# SENSE.net
KiCad netlist of a schematic drawn in Altium Designer
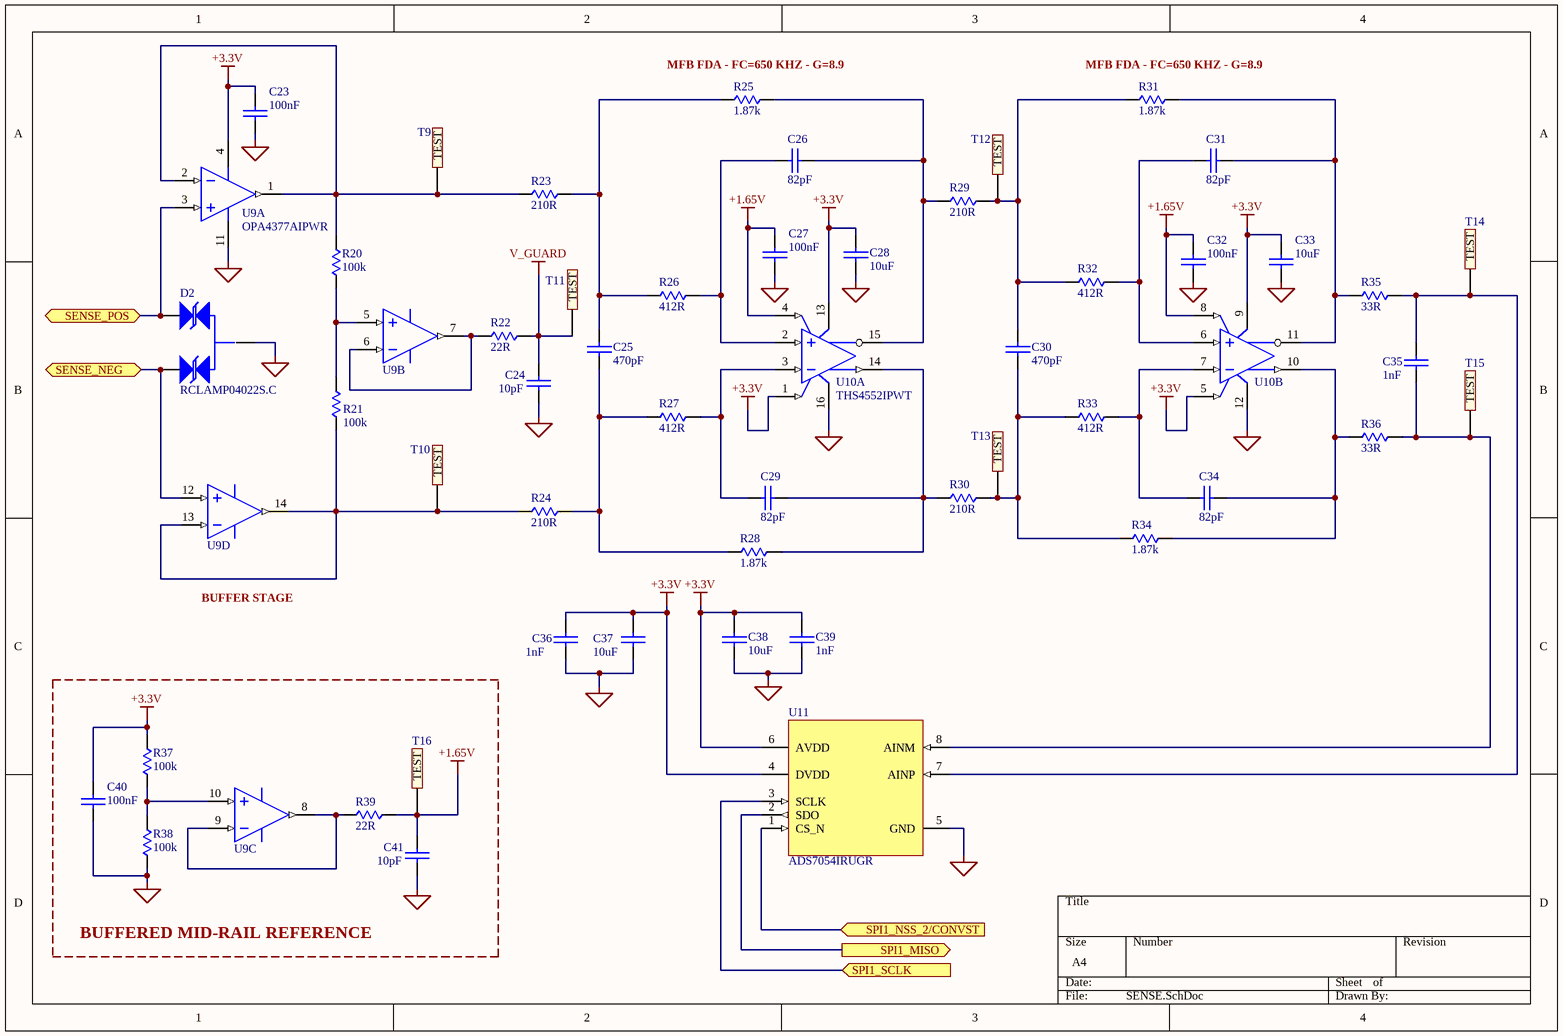
[diagram p0: SENSE.SchDoc]

(export (version "E")
  (design (tool "Eeschema 10.0.6"))
  (components
    (comp (ref "C23")
      (value "100nF")
      (footprint "0603-CAP")
      (description "CAP CER 100 NF 50V X7R 0603")
      (libsource (lib "SGL_Capacitors") (part "Capacitor"))
    )
    (comp (ref "C24")
      (value "10pF")
      (footprint "0603-CAP")
      (description "CAP CER 10PF 50V C0G/NPO 0603")
      (libsource (lib "SGL_Capacitors") (part "Capacitor"))
    )
    (comp (ref "C25")
      (value "470pF")
      (footprint "0603-CAP")
      (description "CAP CER 470PF 50V C0G 0603")
      (libsource (lib "SGL_Capacitors") (part "Capacitor"))
    )
    (comp (ref "C26")
      (value "82pF")
      (footprint "0603-CAP")
      (description "CAP CER 82PF 50V C0G 0603")
      (libsource (lib "SGL_Capacitors") (part "Capacitor"))
    )
    (comp (ref "C27")
      (value "100nF")
      (footprint "0603-CAP")
      (description "CAP CER 100 NF 50V X7R 0603")
      (libsource (lib "SGL_Capacitors") (part "Capacitor"))
    )
    (comp (ref "C28")
      (value "10uF")
      (footprint "0603-CAP")
      (description "CAP CER 10uF 6.3V X5R 0603")
      (libsource (lib "SGL_Capacitors") (part "Capacitor"))
    )
    (comp (ref "C29")
      (value "82pF")
      (footprint "0603-CAP")
      (description "CAP CER 82PF 50V C0G 0603")
      (libsource (lib "SGL_Capacitors") (part "Capacitor"))
    )
    (comp (ref "C30")
      (value "470pF")
      (footprint "0603-CAP")
      (description "CAP CER 470PF 50V C0G 0603")
      (libsource (lib "SGL_Capacitors") (part "Capacitor"))
    )
    (comp (ref "C31")
      (value "82pF")
      (footprint "0603-CAP")
      (description "CAP CER 82PF 50V C0G 0603")
      (libsource (lib "SGL_Capacitors") (part "Capacitor"))
    )
    (comp (ref "C32")
      (value "100nF")
      (footprint "0603-CAP")
      (description "CAP CER 100 NF 50V X7R 0603")
      (libsource (lib "SGL_Capacitors") (part "Capacitor"))
    )
    (comp (ref "C33")
      (value "10uF")
      (footprint "0603-CAP")
      (description "CAP CER 10uF 6.3V X5R 0603")
      (libsource (lib "SGL_Capacitors") (part "Capacitor"))
    )
    (comp (ref "C34")
      (value "82pF")
      (footprint "0603-CAP")
      (description "CAP CER 82PF 50V C0G 0603")
      (libsource (lib "SGL_Capacitors") (part "Capacitor"))
    )
    (comp (ref "C35")
      (value "1nF")
      (footprint "0603-CAP")
      (description "CAP CER 1000 PF 50V C0G 0603")
      (libsource (lib "SGL_Capacitors") (part "Capacitor"))
    )
    (comp (ref "C36")
      (value "1nF")
      (footprint "0603-CAP")
      (description "CAP CER 1000 PF 50V C0G 0603")
      (libsource (lib "SGL_Capacitors") (part "Capacitor"))
    )
    (comp (ref "C37")
      (value "10uF")
      (footprint "0603-CAP")
      (description "CAP CER 10uF 6.3V X5R 0603")
      (libsource (lib "SGL_Capacitors") (part "Capacitor"))
    )
    (comp (ref "C38")
      (value "10uF")
      (footprint "0603-CAP")
      (description "CAP CER 10uF 6.3V X5R 0603")
      (libsource (lib "SGL_Capacitors") (part "Capacitor"))
    )
    (comp (ref "C39")
      (value "1nF")
      (footprint "0603-CAP")
      (description "CAP CER 1000 PF 50V C0G 0603")
      (libsource (lib "SGL_Capacitors") (part "Capacitor"))
    )
    (comp (ref "C40")
      (value "100nF")
      (footprint "0603-CAP")
      (description "CAP CER 100 NF 50V X7R 0603")
      (libsource (lib "SGL_Capacitors") (part "Capacitor"))
    )
    (comp (ref "C41")
      (value "10pF")
      (footprint "0603-CAP")
      (description "CAP CER 10PF 50V C0G/NPO 0603")
      (libsource (lib "SGL_Capacitors") (part "Capacitor"))
    )
    (comp (ref "D2")
      (value "RCLAMP04022S.C")
      (footprint "SOT-23 3L")
      (libsource (lib "BioZ") (part "RCLAMP04022S.C"))
    )
    (comp (ref "R20")
      (value "100k")
      (footprint "0603-RES")
      (description "RES SMD 100KOHM 0.1% 1/10W 0603")
      (libsource (lib "SGL_Resistives") (part "RESISTOR"))
    )
    (comp (ref "R21")
      (value "100k")
      (footprint "0603-RES")
      (description "RES SMD 100KOHM 0.1% 1/10W 0603")
      (libsource (lib "SGL_Resistives") (part "RESISTOR"))
    )
    (comp (ref "R22")
      (value "22R")
      (footprint "0603-RES")
      (description "RES SMD 22OHM 0.1% 1/10W 0603")
      (libsource (lib "SGL_Resistives") (part "RESISTOR"))
    )
    (comp (ref "R23")
      (value "210R")
      (footprint "0603-RES")
      (description "RES SMD 210OHM 0.1% 1/10W 0603")
      (libsource (lib "SGL_Resistives") (part "RESISTOR"))
    )
    (comp (ref "R24")
      (value "210R")
      (footprint "0603-RES")
      (description "RES SMD 210OHM 0.1% 1/10W 0603")
      (libsource (lib "SGL_Resistives") (part "RESISTOR"))
    )
    (comp (ref "R25")
      (value "1.87k")
      (footprint "0603-RES")
      (description "RES SMD 1.87KOHM 0.1% 1/10W 0603")
      (libsource (lib "SGL_Resistives") (part "RESISTOR"))
    )
    (comp (ref "R26")
      (value "412R")
      (footprint "0603-RES")
      (description "RES SMD 412OHM 0.1% 1/10W 0603")
      (libsource (lib "SGL_Resistives") (part "RESISTOR"))
    )
    (comp (ref "R27")
      (value "412R")
      (footprint "0603-RES")
      (description "RES SMD 412OHM 0.1% 1/10W 0603")
      (libsource (lib "SGL_Resistives") (part "RESISTOR"))
    )
    (comp (ref "R28")
      (value "1.87k")
      (footprint "0603-RES")
      (description "RES SMD 1.87KOHM 0.1% 1/10W 0603")
      (libsource (lib "SGL_Resistives") (part "RESISTOR"))
    )
    (comp (ref "R29")
      (value "210R")
      (footprint "0603-RES")
      (description "RES SMD 210OHM 0.1% 1/10W 0603")
      (libsource (lib "SGL_Resistives") (part "RESISTOR"))
    )
    (comp (ref "R30")
      (value "210R")
      (footprint "0603-RES")
      (description "RES SMD 210OHM 0.1% 1/10W 0603")
      (libsource (lib "SGL_Resistives") (part "RESISTOR"))
    )
    (comp (ref "R31")
      (value "1.87k")
      (footprint "0603-RES")
      (description "RES SMD 1.87KOHM 0.1% 1/10W 0603")
      (libsource (lib "SGL_Resistives") (part "RESISTOR"))
    )
    (comp (ref "R32")
      (value "412R")
      (footprint "0603-RES")
      (description "RES SMD 412OHM 0.1% 1/10W 0603")
      (libsource (lib "SGL_Resistives") (part "RESISTOR"))
    )
    (comp (ref "R33")
      (value "412R")
      (footprint "0603-RES")
      (description "RES SMD 412OHM 0.1% 1/10W 0603")
      (libsource (lib "SGL_Resistives") (part "RESISTOR"))
    )
    (comp (ref "R34")
      (value "1.87k")
      (footprint "0603-RES")
      (description "RES SMD 1.87KOHM 0.1% 1/10W 0603")
      (libsource (lib "SGL_Resistives") (part "RESISTOR"))
    )
    (comp (ref "R35")
      (value "33R")
      (footprint "0603-RES")
      (description "RES SMD 33OHM 0.1% 1/10W 0603")
      (libsource (lib "SGL_Resistives") (part "RESISTOR"))
    )
    (comp (ref "R36")
      (value "33R")
      (footprint "0603-RES")
      (description "RES SMD 33OHM 0.1% 1/10W 0603")
      (libsource (lib "SGL_Resistives") (part "RESISTOR"))
    )
    (comp (ref "R37")
      (value "100k")
      (footprint "0603-RES")
      (description "RES SMD 100KOHM 0.1% 1/10W 0603")
      (libsource (lib "SGL_Resistives") (part "RESISTOR"))
    )
    (comp (ref "R38")
      (value "100k")
      (footprint "0603-RES")
      (description "RES SMD 100KOHM 0.1% 1/10W 0603")
      (libsource (lib "SGL_Resistives") (part "RESISTOR"))
    )
    (comp (ref "R39")
      (value "22R")
      (footprint "0603-RES")
      (description "RES SMD 22OHM 0.1% 1/10W 0603")
      (libsource (lib "SGL_Resistives") (part "RESISTOR"))
    )
    (comp (ref "T9")
      (value "5002K")
      (footprint "TESTPOINT White")
      (description "PC TEST POINT MINIATURE WHITE")
      (libsource (lib "SGL_Connectors") (part "Testpoint white"))
    )
    (comp (ref "T10")
      (value "5002K")
      (footprint "TESTPOINT White")
      (description "PC TEST POINT MINIATURE WHITE")
      (libsource (lib "SGL_Connectors") (part "Testpoint white"))
    )
    (comp (ref "T11")
      (value "5002K")
      (footprint "TESTPOINT White")
      (description "PC TEST POINT MINIATURE WHITE")
      (libsource (lib "SGL_Connectors") (part "Testpoint white"))
    )
    (comp (ref "T12")
      (value "5002K")
      (footprint "TESTPOINT White")
      (description "PC TEST POINT MINIATURE WHITE")
      (libsource (lib "SGL_Connectors") (part "Testpoint white"))
    )
    (comp (ref "T13")
      (value "5002K")
      (footprint "TESTPOINT White")
      (description "PC TEST POINT MINIATURE WHITE")
      (libsource (lib "SGL_Connectors") (part "Testpoint white"))
    )
    (comp (ref "T14")
      (value "5002K")
      (footprint "TESTPOINT White")
      (description "PC TEST POINT MINIATURE WHITE")
      (libsource (lib "SGL_Connectors") (part "Testpoint white"))
    )
    (comp (ref "T15")
      (value "5002K")
      (footprint "TESTPOINT White")
      (description "PC TEST POINT MINIATURE WHITE")
      (libsource (lib "SGL_Connectors") (part "Testpoint white"))
    )
    (comp (ref "T16")
      (value "5002K")
      (footprint "TESTPOINT White")
      (description "PC TEST POINT MINIATURE WHITE")
      (libsource (lib "SGL_Connectors") (part "Testpoint white"))
    )
    (comp (ref "U9")
      (value "OPA4377AIPWR")
      (footprint "PW0014A_N")
      (fields (field (name "MANUFACTURER") "Texas Instruments"))
      (libsource (lib "Altium Content Vault") (part "TI-OPA16X4_4XXX-14"))
    )
    (comp (ref "U10")
      (value "THS4552IPWT")
      (footprint "PW0016A_N")
      (description "Dual Channel, Low-Noise, Precision, 150-MHz, Fully Differential Amplifier 16-TSSOP -40 to 125")
      (fields (field (name "COPYRIGHT") "Copyright (C) 2025 Ultra Librarian. All rights reserved."))
      (libsource (lib "") (part "THS4552IPWT_1"))
    )
    (comp (ref "U11")
      (value "ADS7054IRUGR")
      (footprint "8-X2QFN (1.5x1.5)")
      (description "14-Bit, 1MSPS, Differential Input, Small-Size Low-Power SAR ADC 8-X2QFN -40 to 125")
      (fields (field (name "COPYRIGHT") "Copyright (C) 2026 Ultra Librarian. All rights reserved."))
      (libsource (lib "BioZ") (part "ADS7054IRUGR"))
    )
  )
  (nets
    (net (code "1") (name "+1.65V") (class "Default")
      (node (ref "C27") (pin "1") (pinfunction "1_1") (pintype "passive"))
      (node (ref "C32") (pin "1") (pinfunction "1_1") (pintype "passive"))
      (node (ref "C41") (pin "1") (pinfunction "1_1") (pintype "passive"))
      (node (ref "R39") (pin "2") (pinfunction "2_2") (pintype "passive"))
      (node (ref "T16") (pin "1") (pinfunction "TEST_1") (pintype "passive"))
      (node (ref "U10") (pin "4") (pinfunction "VOCM1_4") (pintype "input"))
      (node (ref "U10") (pin "8") (pinfunction "VOCM2_8") (pintype "input"))
    )
    (net (code "2") (name "+3.3V") (class "Default")
      (node (ref "C23") (pin "1") (pinfunction "1_1") (pintype "passive"))
      (node (ref "C28") (pin "1") (pinfunction "1_1") (pintype "passive"))
      (node (ref "C33") (pin "1") (pinfunction "1_1") (pintype "passive"))
      (node (ref "C36") (pin "1") (pinfunction "1_1") (pintype "passive"))
      (node (ref "C37") (pin "1") (pinfunction "1_1") (pintype "passive"))
      (node (ref "C38") (pin "1") (pinfunction "1_1") (pintype "passive"))
      (node (ref "C39") (pin "1") (pinfunction "1_1") (pintype "passive"))
      (node (ref "C40") (pin "1") (pinfunction "1_1") (pintype "passive"))
      (node (ref "R37") (pin "2") (pinfunction "2_2") (pintype "passive"))
      (node (ref "U10") (pin "1") (pinfunction "PD1_N_1") (pintype "input"))
      (node (ref "U10") (pin "13") (pinfunction "VS1+_13") (pintype "power_in"))
      (node (ref "U10") (pin "5") (pinfunction "PD2_N_5") (pintype "input"))
      (node (ref "U10") (pin "9") (pinfunction "VS2+_9") (pintype "power_in"))
      (node (ref "U11") (pin "4") (pinfunction "DVDD_4") (pintype "power_in"))
      (node (ref "U11") (pin "6") (pinfunction "AVDD_6") (pintype "power_in"))
      (node (ref "U9") (pin "4") (pinfunction "V+_4") (pintype "power_in"))
    )
    (net (code "3") (name "/SENSE_NEG") (class "Default")
      (node (ref "D2") (pin "2") (pinfunction "2_2") (pintype "passive"))
      (node (ref "U9") (pin "12") (pinfunction "IN_D+_12") (pintype "input"))
    )
    (net (code "4") (name "/SENSE_POS") (class "Default")
      (node (ref "D2") (pin "1") (pinfunction "1_1") (pintype "passive"))
      (node (ref "U9") (pin "3") (pinfunction "IN_A+_3") (pintype "input"))
    )
    (net (code "5") (name "/SPI1_MISO") (class "Default")
      (node (ref "U11") (pin "2") (pinfunction "SDO_2") (pintype "output"))
    )
    (net (code "6") (name "/SPI1_NSS_2{slash}CONVST") (class "Default")
      (node (ref "U11") (pin "1") (pinfunction "CS_N_1") (pintype "input"))
    )
    (net (code "7") (name "/SPI1_SCLK") (class "Default")
      (node (ref "U11") (pin "3") (pinfunction "SCLK_3") (pintype "input"))
    )
    (net (code "8") (name "GND") (class "Default")
      (node (ref "C23") (pin "2") (pinfunction "2_2") (pintype "passive"))
      (node (ref "C24") (pin "2") (pinfunction "2_2") (pintype "passive"))
      (node (ref "C27") (pin "2") (pinfunction "2_2") (pintype "passive"))
      (node (ref "C28") (pin "2") (pinfunction "2_2") (pintype "passive"))
      (node (ref "C32") (pin "2") (pinfunction "2_2") (pintype "passive"))
      (node (ref "C33") (pin "2") (pinfunction "2_2") (pintype "passive"))
      (node (ref "C36") (pin "2") (pinfunction "2_2") (pintype "passive"))
      (node (ref "C37") (pin "2") (pinfunction "2_2") (pintype "passive"))
      (node (ref "C38") (pin "2") (pinfunction "2_2") (pintype "passive"))
      (node (ref "C39") (pin "2") (pinfunction "2_2") (pintype "passive"))
      (node (ref "C40") (pin "2") (pinfunction "2_2") (pintype "passive"))
      (node (ref "C41") (pin "2") (pinfunction "2_2") (pintype "passive"))
      (node (ref "D2") (pin "3") (pinfunction "3_3") (pintype "passive"))
      (node (ref "R38") (pin "1") (pinfunction "1_1") (pintype "passive"))
      (node (ref "U10") (pin "12") (pinfunction "VS-_12") (pintype "power_in"))
      (node (ref "U10") (pin "16") (pinfunction "VS-_16") (pintype "power_in"))
      (node (ref "U11") (pin "5") (pinfunction "GND_5") (pintype "power_in"))
      (node (ref "U9") (pin "11") (pinfunction "V-_11") (pintype "power_in"))
    )
    (net (code "9") (name "Net-(C25-Pad1)") (class "Default")
      (node (ref "C25") (pin "1") (pinfunction "1_1") (pintype "passive"))
      (node (ref "R24") (pin "2") (pinfunction "2_2") (pintype "passive"))
      (node (ref "R27") (pin "1") (pinfunction "1_1") (pintype "passive"))
      (node (ref "R28") (pin "1") (pinfunction "1_1") (pintype "passive"))
    )
    (net (code "10") (name "Net-(C25-Pad2)") (class "Default")
      (node (ref "C25") (pin "2") (pinfunction "2_2") (pintype "passive"))
      (node (ref "R23") (pin "2") (pinfunction "2_2") (pintype "passive"))
      (node (ref "R25") (pin "1") (pinfunction "1_1") (pintype "passive"))
      (node (ref "R26") (pin "1") (pinfunction "1_1") (pintype "passive"))
    )
    (net (code "11") (name "Net-(T9-TEST)") (class "Default")
      (node (ref "R20") (pin "2") (pinfunction "2_2") (pintype "passive"))
      (node (ref "R23") (pin "1") (pinfunction "1_1") (pintype "passive"))
      (node (ref "T9") (pin "1") (pinfunction "TEST_1") (pintype "passive"))
      (node (ref "U9") (pin "1") (pinfunction "OUT_A_1") (pintype "output"))
      (node (ref "U9") (pin "2") (pinfunction "IN_A-_2") (pintype "input"))
    )
    (net (code "12") (name "Net-(T10-TEST)") (class "Default")
      (node (ref "R21") (pin "1") (pinfunction "1_1") (pintype "passive"))
      (node (ref "R24") (pin "1") (pinfunction "1_1") (pintype "passive"))
      (node (ref "T10") (pin "1") (pinfunction "TEST_1") (pintype "passive"))
      (node (ref "U9") (pin "13") (pinfunction "IN_D-_13") (pintype "input"))
      (node (ref "U9") (pin "14") (pinfunction "OUT_D_14") (pintype "output"))
    )
    (net (code "13") (name "Net-(T12-TEST)") (class "Default")
      (node (ref "C30") (pin "2") (pinfunction "2_2") (pintype "passive"))
      (node (ref "R29") (pin "2") (pinfunction "2_2") (pintype "passive"))
      (node (ref "R31") (pin "1") (pinfunction "1_1") (pintype "passive"))
      (node (ref "R32") (pin "1") (pinfunction "1_1") (pintype "passive"))
      (node (ref "T12") (pin "1") (pinfunction "TEST_1") (pintype "passive"))
    )
    (net (code "14") (name "Net-(T13-TEST)") (class "Default")
      (node (ref "C30") (pin "1") (pinfunction "1_1") (pintype "passive"))
      (node (ref "R30") (pin "2") (pinfunction "2_2") (pintype "passive"))
      (node (ref "R33") (pin "1") (pinfunction "1_1") (pintype "passive"))
      (node (ref "R34") (pin "1") (pinfunction "1_1") (pintype "passive"))
      (node (ref "T13") (pin "1") (pinfunction "TEST_1") (pintype "passive"))
    )
    (net (code "15") (name "Net-(T14-TEST)") (class "Default")
      (node (ref "C35") (pin "1") (pinfunction "1_1") (pintype "passive"))
      (node (ref "R35") (pin "2") (pinfunction "2_2") (pintype "passive"))
      (node (ref "T14") (pin "1") (pinfunction "TEST_1") (pintype "passive"))
      (node (ref "U11") (pin "7") (pinfunction "AINP_7") (pintype "input"))
    )
    (net (code "16") (name "Net-(T15-TEST)") (class "Default")
      (node (ref "C35") (pin "2") (pinfunction "2_2") (pintype "passive"))
      (node (ref "R36") (pin "2") (pinfunction "2_2") (pintype "passive"))
      (node (ref "T15") (pin "1") (pinfunction "TEST_1") (pintype "passive"))
      (node (ref "U11") (pin "8") (pinfunction "AINM_8") (pintype "input"))
    )
    (net (code "17") (name "Net-(U9B-IN_B+)") (class "Default")
      (node (ref "R20") (pin "1") (pinfunction "1_1") (pintype "passive"))
      (node (ref "R21") (pin "2") (pinfunction "2_2") (pintype "passive"))
      (node (ref "U9") (pin "5") (pinfunction "IN_B+_5") (pintype "input"))
    )
    (net (code "18") (name "Net-(U9B-IN_B-)") (class "Default")
      (node (ref "R22") (pin "1") (pinfunction "1_1") (pintype "passive"))
      (node (ref "U9") (pin "6") (pinfunction "IN_B-_6") (pintype "input"))
      (node (ref "U9") (pin "7") (pinfunction "OUT_B_7") (pintype "output"))
    )
    (net (code "19") (name "Net-(U9C-IN_C+)") (class "Default")
      (node (ref "R37") (pin "1") (pinfunction "1_1") (pintype "passive"))
      (node (ref "R38") (pin "2") (pinfunction "2_2") (pintype "passive"))
      (node (ref "U9") (pin "10") (pinfunction "IN_C+_10") (pintype "input"))
    )
    (net (code "20") (name "Net-(U9C-IN_C-)") (class "Default")
      (node (ref "R39") (pin "1") (pinfunction "1_1") (pintype "passive"))
      (node (ref "U9") (pin "8") (pinfunction "OUT_C_8") (pintype "output"))
      (node (ref "U9") (pin "9") (pinfunction "IN_C-_9") (pintype "input"))
    )
    (net (code "21") (name "Net-(U10A-VIN1+)") (class "Default")
      (node (ref "C26") (pin "1") (pinfunction "1_1") (pintype "passive"))
      (node (ref "R26") (pin "2") (pinfunction "2_2") (pintype "passive"))
      (node (ref "U10") (pin "2") (pinfunction "VIN1+_2") (pintype "input"))
    )
    (net (code "22") (name "Net-(U10A-VIN1-)") (class "Default")
      (node (ref "C29") (pin "1") (pinfunction "1_1") (pintype "passive"))
      (node (ref "R27") (pin "2") (pinfunction "2_2") (pintype "passive"))
      (node (ref "U10") (pin "3") (pinfunction "VIN1-_3") (pintype "input"))
    )
    (net (code "23") (name "Net-(U10A-VOUT1+)") (class "Default")
      (node (ref "C29") (pin "2") (pinfunction "2_2") (pintype "passive"))
      (node (ref "R28") (pin "2") (pinfunction "2_2") (pintype "passive"))
      (node (ref "R30") (pin "1") (pinfunction "1_1") (pintype "passive"))
      (node (ref "U10") (pin "14") (pinfunction "VOUT1+_14") (pintype "output"))
    )
    (net (code "24") (name "Net-(U10A-VOUT1-)") (class "Default")
      (node (ref "C26") (pin "2") (pinfunction "2_2") (pintype "passive"))
      (node (ref "R25") (pin "2") (pinfunction "2_2") (pintype "passive"))
      (node (ref "R29") (pin "1") (pinfunction "1_1") (pintype "passive"))
      (node (ref "U10") (pin "15") (pinfunction "VOUT1-_15") (pintype "passive"))
    )
    (net (code "25") (name "Net-(U10B-VIN2+)") (class "Default")
      (node (ref "C31") (pin "1") (pinfunction "1_1") (pintype "passive"))
      (node (ref "R32") (pin "2") (pinfunction "2_2") (pintype "passive"))
      (node (ref "U10") (pin "6") (pinfunction "VIN2+_6") (pintype "input"))
    )
    (net (code "26") (name "Net-(U10B-VIN2-)") (class "Default")
      (node (ref "C34") (pin "1") (pinfunction "1_1") (pintype "passive"))
      (node (ref "R33") (pin "2") (pinfunction "2_2") (pintype "passive"))
      (node (ref "U10") (pin "7") (pinfunction "VIN2-_7") (pintype "input"))
    )
    (net (code "27") (name "Net-(U10B-VOUT2+)") (class "Default")
      (node (ref "C34") (pin "2") (pinfunction "2_2") (pintype "passive"))
      (node (ref "R34") (pin "2") (pinfunction "2_2") (pintype "passive"))
      (node (ref "R36") (pin "1") (pinfunction "1_1") (pintype "passive"))
      (node (ref "U10") (pin "10") (pinfunction "VOUT2+_10") (pintype "output"))
    )
    (net (code "28") (name "Net-(U10B-VOUT2-)") (class "Default")
      (node (ref "C31") (pin "2") (pinfunction "2_2") (pintype "passive"))
      (node (ref "R31") (pin "2") (pinfunction "2_2") (pintype "passive"))
      (node (ref "R35") (pin "1") (pinfunction "1_1") (pintype "passive"))
      (node (ref "U10") (pin "11") (pinfunction "VOUT2-_11") (pintype "passive"))
    )
    (net (code "29") (name "V_GUARD") (class "Default")
      (node (ref "C24") (pin "1") (pinfunction "1_1") (pintype "passive"))
      (node (ref "R22") (pin "2") (pinfunction "2_2") (pintype "passive"))
      (node (ref "T11") (pin "1") (pinfunction "TEST_1") (pintype "passive"))
    )
  )
)
